# picstick_shield_v1.net
KiCad netlist of a schematic drawn in EAGLE
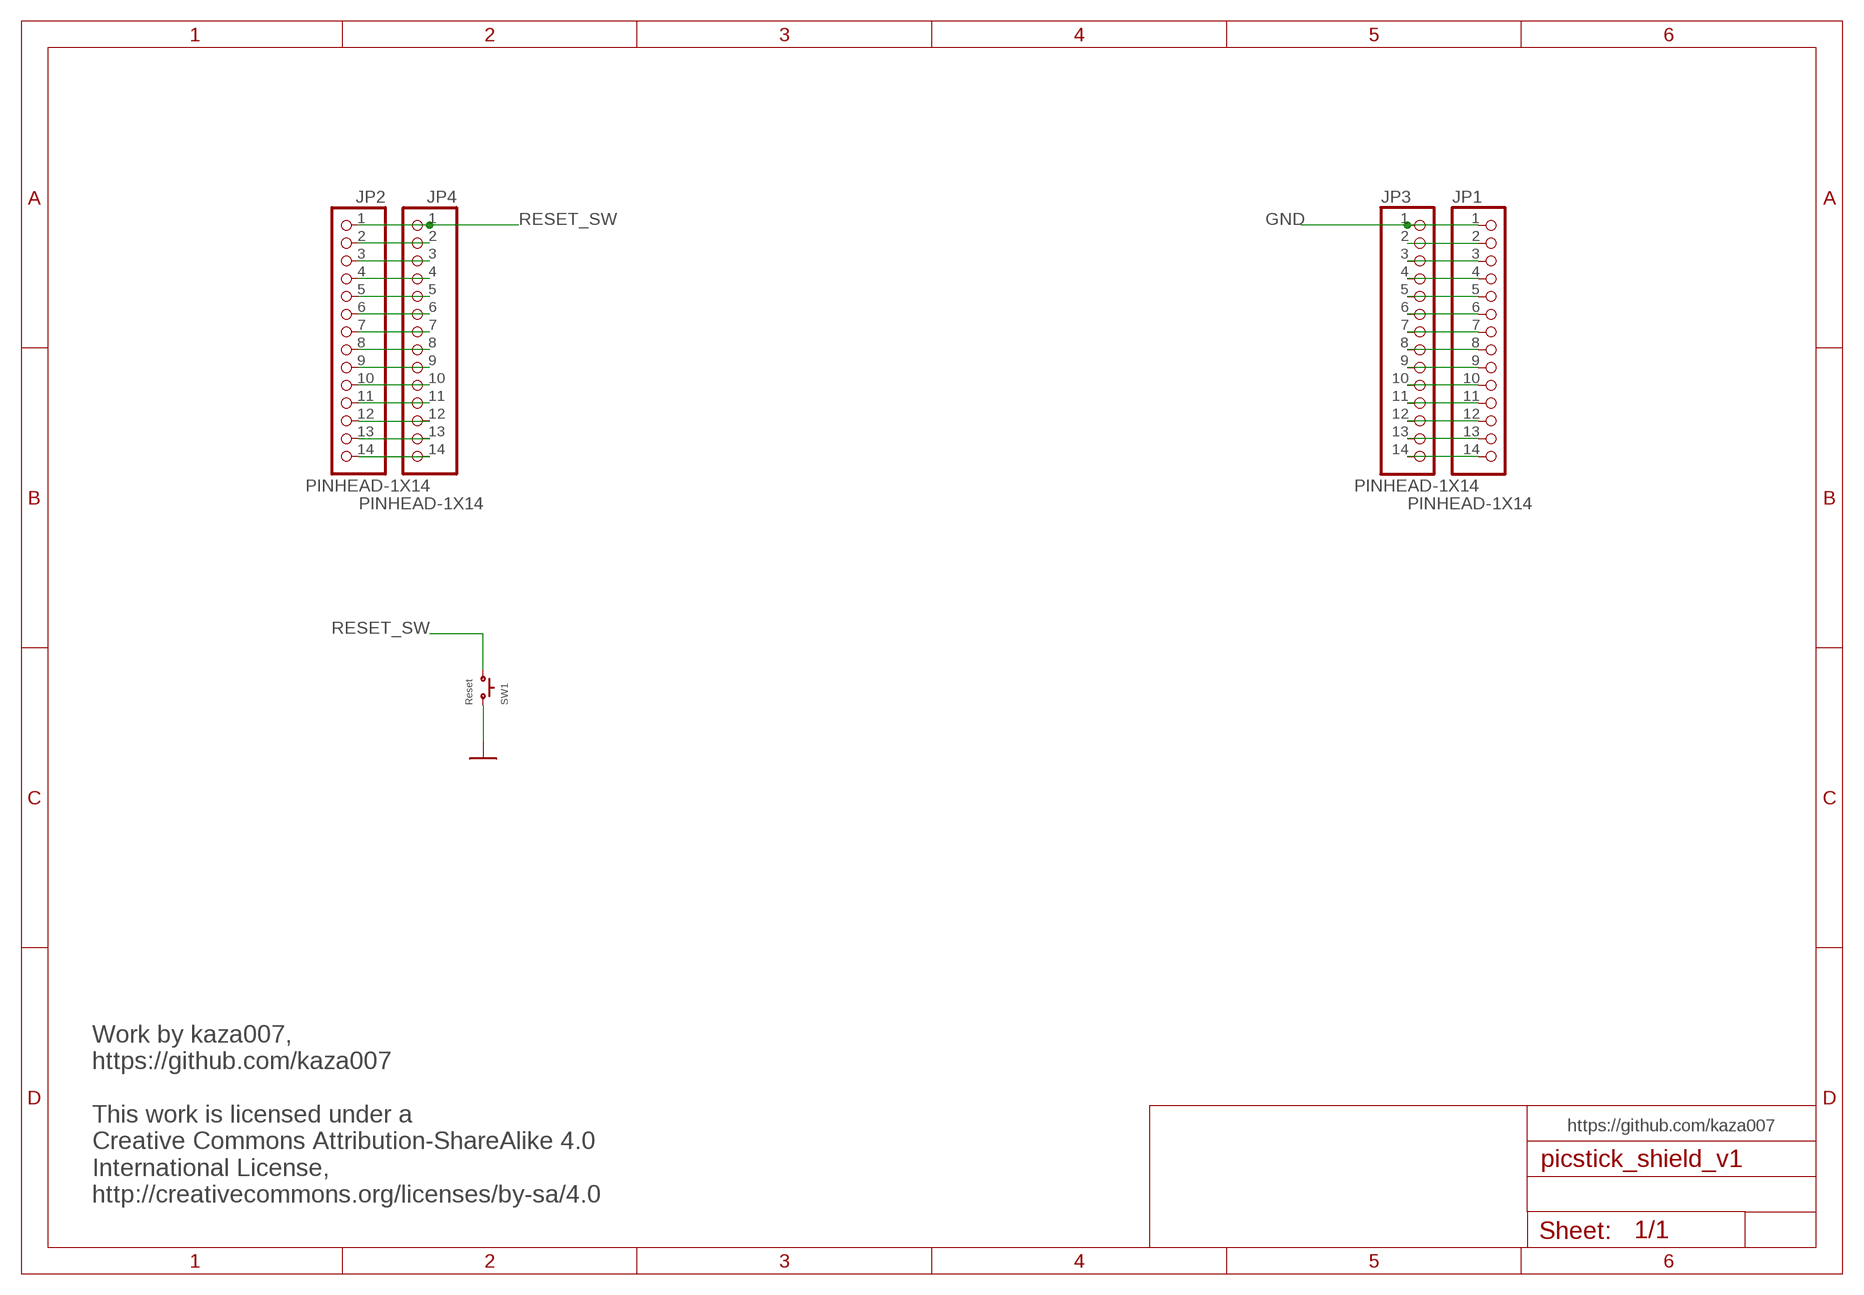
[diagram p0: schematic, sheet 1]

(export (version "E")
  (design (tool "Eeschema 10.0.6"))
  (components
    (comp (ref "JP1")
      (value "PINHEAD-1X14")
      (footprint "eagle-import:PINHEAD-1X14")
      (libsource (lib "eagle-import") (part "PINHEAD-1X14"))
    )
    (comp (ref "JP2")
      (value "PINHEAD-1X14")
      (footprint "eagle-import:PINHEAD-1X14")
      (libsource (lib "eagle-import") (part "PINHEAD-1X14"))
    )
    (comp (ref "JP3")
      (value "PINHEAD-1X14")
      (footprint "eagle-import:PINHEAD-1X14")
      (libsource (lib "eagle-import") (part "PINHEAD-1X14"))
    )
    (comp (ref "JP4")
      (value "PINHEAD-1X14")
      (footprint "eagle-import:PINHEAD-1X14")
      (libsource (lib "eagle-import") (part "PINHEAD-1X14"))
    )
    (comp (ref "SW1")
      (value "Reset")
      (footprint "eagle-import:SKHLAAA010")
      (libsource (lib "eagle-import") (part "SKHLAAA010"))
    )
  )
  (nets
    (net (code "1") (name "/RESET_SW") (class "Default")
      (node (ref "JP2") (pin "1") (pinfunction "1_1") (pintype "passive"))
      (node (ref "JP4") (pin "1") (pinfunction "1_1") (pintype "passive"))
      (node (ref "SW1") (pin "2") (pinfunction "2_2") (pintype "bidirectional"))
    )
    (net (code "2") (name "Net-(JP1-Pad2)") (class "Default")
      (node (ref "JP1") (pin "2") (pinfunction "2_2") (pintype "passive"))
      (node (ref "JP3") (pin "2") (pinfunction "2_2") (pintype "passive"))
    )
    (net (code "3") (name "Net-(JP1-Pad3)") (class "Default")
      (node (ref "JP1") (pin "3") (pinfunction "3_3") (pintype "passive"))
      (node (ref "JP3") (pin "3") (pinfunction "3_3") (pintype "passive"))
    )
    (net (code "4") (name "Net-(JP1-Pad4)") (class "Default")
      (node (ref "JP1") (pin "4") (pinfunction "4_4") (pintype "passive"))
      (node (ref "JP3") (pin "4") (pinfunction "4_4") (pintype "passive"))
    )
    (net (code "5") (name "Net-(JP1-Pad5)") (class "Default")
      (node (ref "JP1") (pin "5") (pinfunction "5_5") (pintype "passive"))
      (node (ref "JP3") (pin "5") (pinfunction "5_5") (pintype "passive"))
    )
    (net (code "6") (name "Net-(JP1-Pad6)") (class "Default")
      (node (ref "JP1") (pin "6") (pinfunction "6_6") (pintype "passive"))
      (node (ref "JP3") (pin "6") (pinfunction "6_6") (pintype "passive"))
    )
    (net (code "7") (name "Net-(JP1-Pad7)") (class "Default")
      (node (ref "JP1") (pin "7") (pinfunction "7_7") (pintype "passive"))
      (node (ref "JP3") (pin "7") (pinfunction "7_7") (pintype "passive"))
    )
    (net (code "8") (name "Net-(JP1-Pad8)") (class "Default")
      (node (ref "JP1") (pin "8") (pinfunction "8_8") (pintype "passive"))
      (node (ref "JP3") (pin "8") (pinfunction "8_8") (pintype "passive"))
    )
    (net (code "9") (name "Net-(JP1-Pad9)") (class "Default")
      (node (ref "JP1") (pin "9") (pinfunction "9_9") (pintype "passive"))
      (node (ref "JP3") (pin "9") (pinfunction "9_9") (pintype "passive"))
    )
    (net (code "10") (name "Net-(JP1-Pad10)") (class "Default")
      (node (ref "JP1") (pin "10") (pinfunction "10_10") (pintype "passive"))
      (node (ref "JP3") (pin "10") (pinfunction "10_10") (pintype "passive"))
    )
    (net (code "11") (name "Net-(JP1-Pad11)") (class "Default")
      (node (ref "JP1") (pin "11") (pinfunction "11_11") (pintype "passive"))
      (node (ref "JP3") (pin "11") (pinfunction "11_11") (pintype "passive"))
    )
    (net (code "12") (name "Net-(JP1-Pad12)") (class "Default")
      (node (ref "JP1") (pin "12") (pinfunction "12_12") (pintype "passive"))
      (node (ref "JP3") (pin "12") (pinfunction "12_12") (pintype "passive"))
    )
    (net (code "13") (name "Net-(JP1-Pad13)") (class "Default")
      (node (ref "JP1") (pin "13") (pinfunction "13_13") (pintype "passive"))
      (node (ref "JP3") (pin "13") (pinfunction "13_13") (pintype "passive"))
    )
    (net (code "14") (name "Net-(JP1-Pad14)") (class "Default")
      (node (ref "JP1") (pin "14") (pinfunction "14_14") (pintype "passive"))
      (node (ref "JP3") (pin "14") (pinfunction "14_14") (pintype "passive"))
    )
    (net (code "15") (name "Net-(JP2-Pad2)") (class "Default")
      (node (ref "JP2") (pin "2") (pinfunction "2_2") (pintype "passive"))
      (node (ref "JP4") (pin "2") (pinfunction "2_2") (pintype "passive"))
    )
    (net (code "16") (name "Net-(JP2-Pad3)") (class "Default")
      (node (ref "JP2") (pin "3") (pinfunction "3_3") (pintype "passive"))
      (node (ref "JP4") (pin "3") (pinfunction "3_3") (pintype "passive"))
    )
    (net (code "17") (name "Net-(JP2-Pad4)") (class "Default")
      (node (ref "JP2") (pin "4") (pinfunction "4_4") (pintype "passive"))
      (node (ref "JP4") (pin "4") (pinfunction "4_4") (pintype "passive"))
    )
    (net (code "18") (name "Net-(JP2-Pad5)") (class "Default")
      (node (ref "JP2") (pin "5") (pinfunction "5_5") (pintype "passive"))
      (node (ref "JP4") (pin "5") (pinfunction "5_5") (pintype "passive"))
    )
    (net (code "19") (name "Net-(JP2-Pad6)") (class "Default")
      (node (ref "JP2") (pin "6") (pinfunction "6_6") (pintype "passive"))
      (node (ref "JP4") (pin "6") (pinfunction "6_6") (pintype "passive"))
    )
    (net (code "20") (name "Net-(JP2-Pad7)") (class "Default")
      (node (ref "JP2") (pin "7") (pinfunction "7_7") (pintype "passive"))
      (node (ref "JP4") (pin "7") (pinfunction "7_7") (pintype "passive"))
    )
    (net (code "21") (name "Net-(JP2-Pad8)") (class "Default")
      (node (ref "JP2") (pin "8") (pinfunction "8_8") (pintype "passive"))
      (node (ref "JP4") (pin "8") (pinfunction "8_8") (pintype "passive"))
    )
    (net (code "22") (name "Net-(JP2-Pad9)") (class "Default")
      (node (ref "JP2") (pin "9") (pinfunction "9_9") (pintype "passive"))
      (node (ref "JP4") (pin "9") (pinfunction "9_9") (pintype "passive"))
    )
    (net (code "23") (name "Net-(JP2-Pad10)") (class "Default")
      (node (ref "JP2") (pin "10") (pinfunction "10_10") (pintype "passive"))
      (node (ref "JP4") (pin "10") (pinfunction "10_10") (pintype "passive"))
    )
    (net (code "24") (name "Net-(JP2-Pad11)") (class "Default")
      (node (ref "JP2") (pin "11") (pinfunction "11_11") (pintype "passive"))
      (node (ref "JP4") (pin "11") (pinfunction "11_11") (pintype "passive"))
    )
    (net (code "25") (name "Net-(JP2-Pad12)") (class "Default")
      (node (ref "JP2") (pin "12") (pinfunction "12_12") (pintype "passive"))
      (node (ref "JP4") (pin "12") (pinfunction "12_12") (pintype "passive"))
    )
    (net (code "26") (name "Net-(JP2-Pad13)") (class "Default")
      (node (ref "JP2") (pin "13") (pinfunction "13_13") (pintype "passive"))
      (node (ref "JP4") (pin "13") (pinfunction "13_13") (pintype "passive"))
    )
    (net (code "27") (name "Net-(JP2-Pad14)") (class "Default")
      (node (ref "JP2") (pin "14") (pinfunction "14_14") (pintype "passive"))
      (node (ref "JP4") (pin "14") (pinfunction "14_14") (pintype "passive"))
    )
    (net (code "28") (name "SUPPLY1_GND") (class "Default")
      (node (ref "JP1") (pin "1") (pinfunction "1_1") (pintype "passive"))
      (node (ref "JP3") (pin "1") (pinfunction "1_1") (pintype "passive"))
      (node (ref "SW1") (pin "1") (pinfunction "1_1") (pintype "bidirectional"))
    )
  )
)
